# Sheet2.net
KiCad netlist of a schematic drawn in Altium Designer
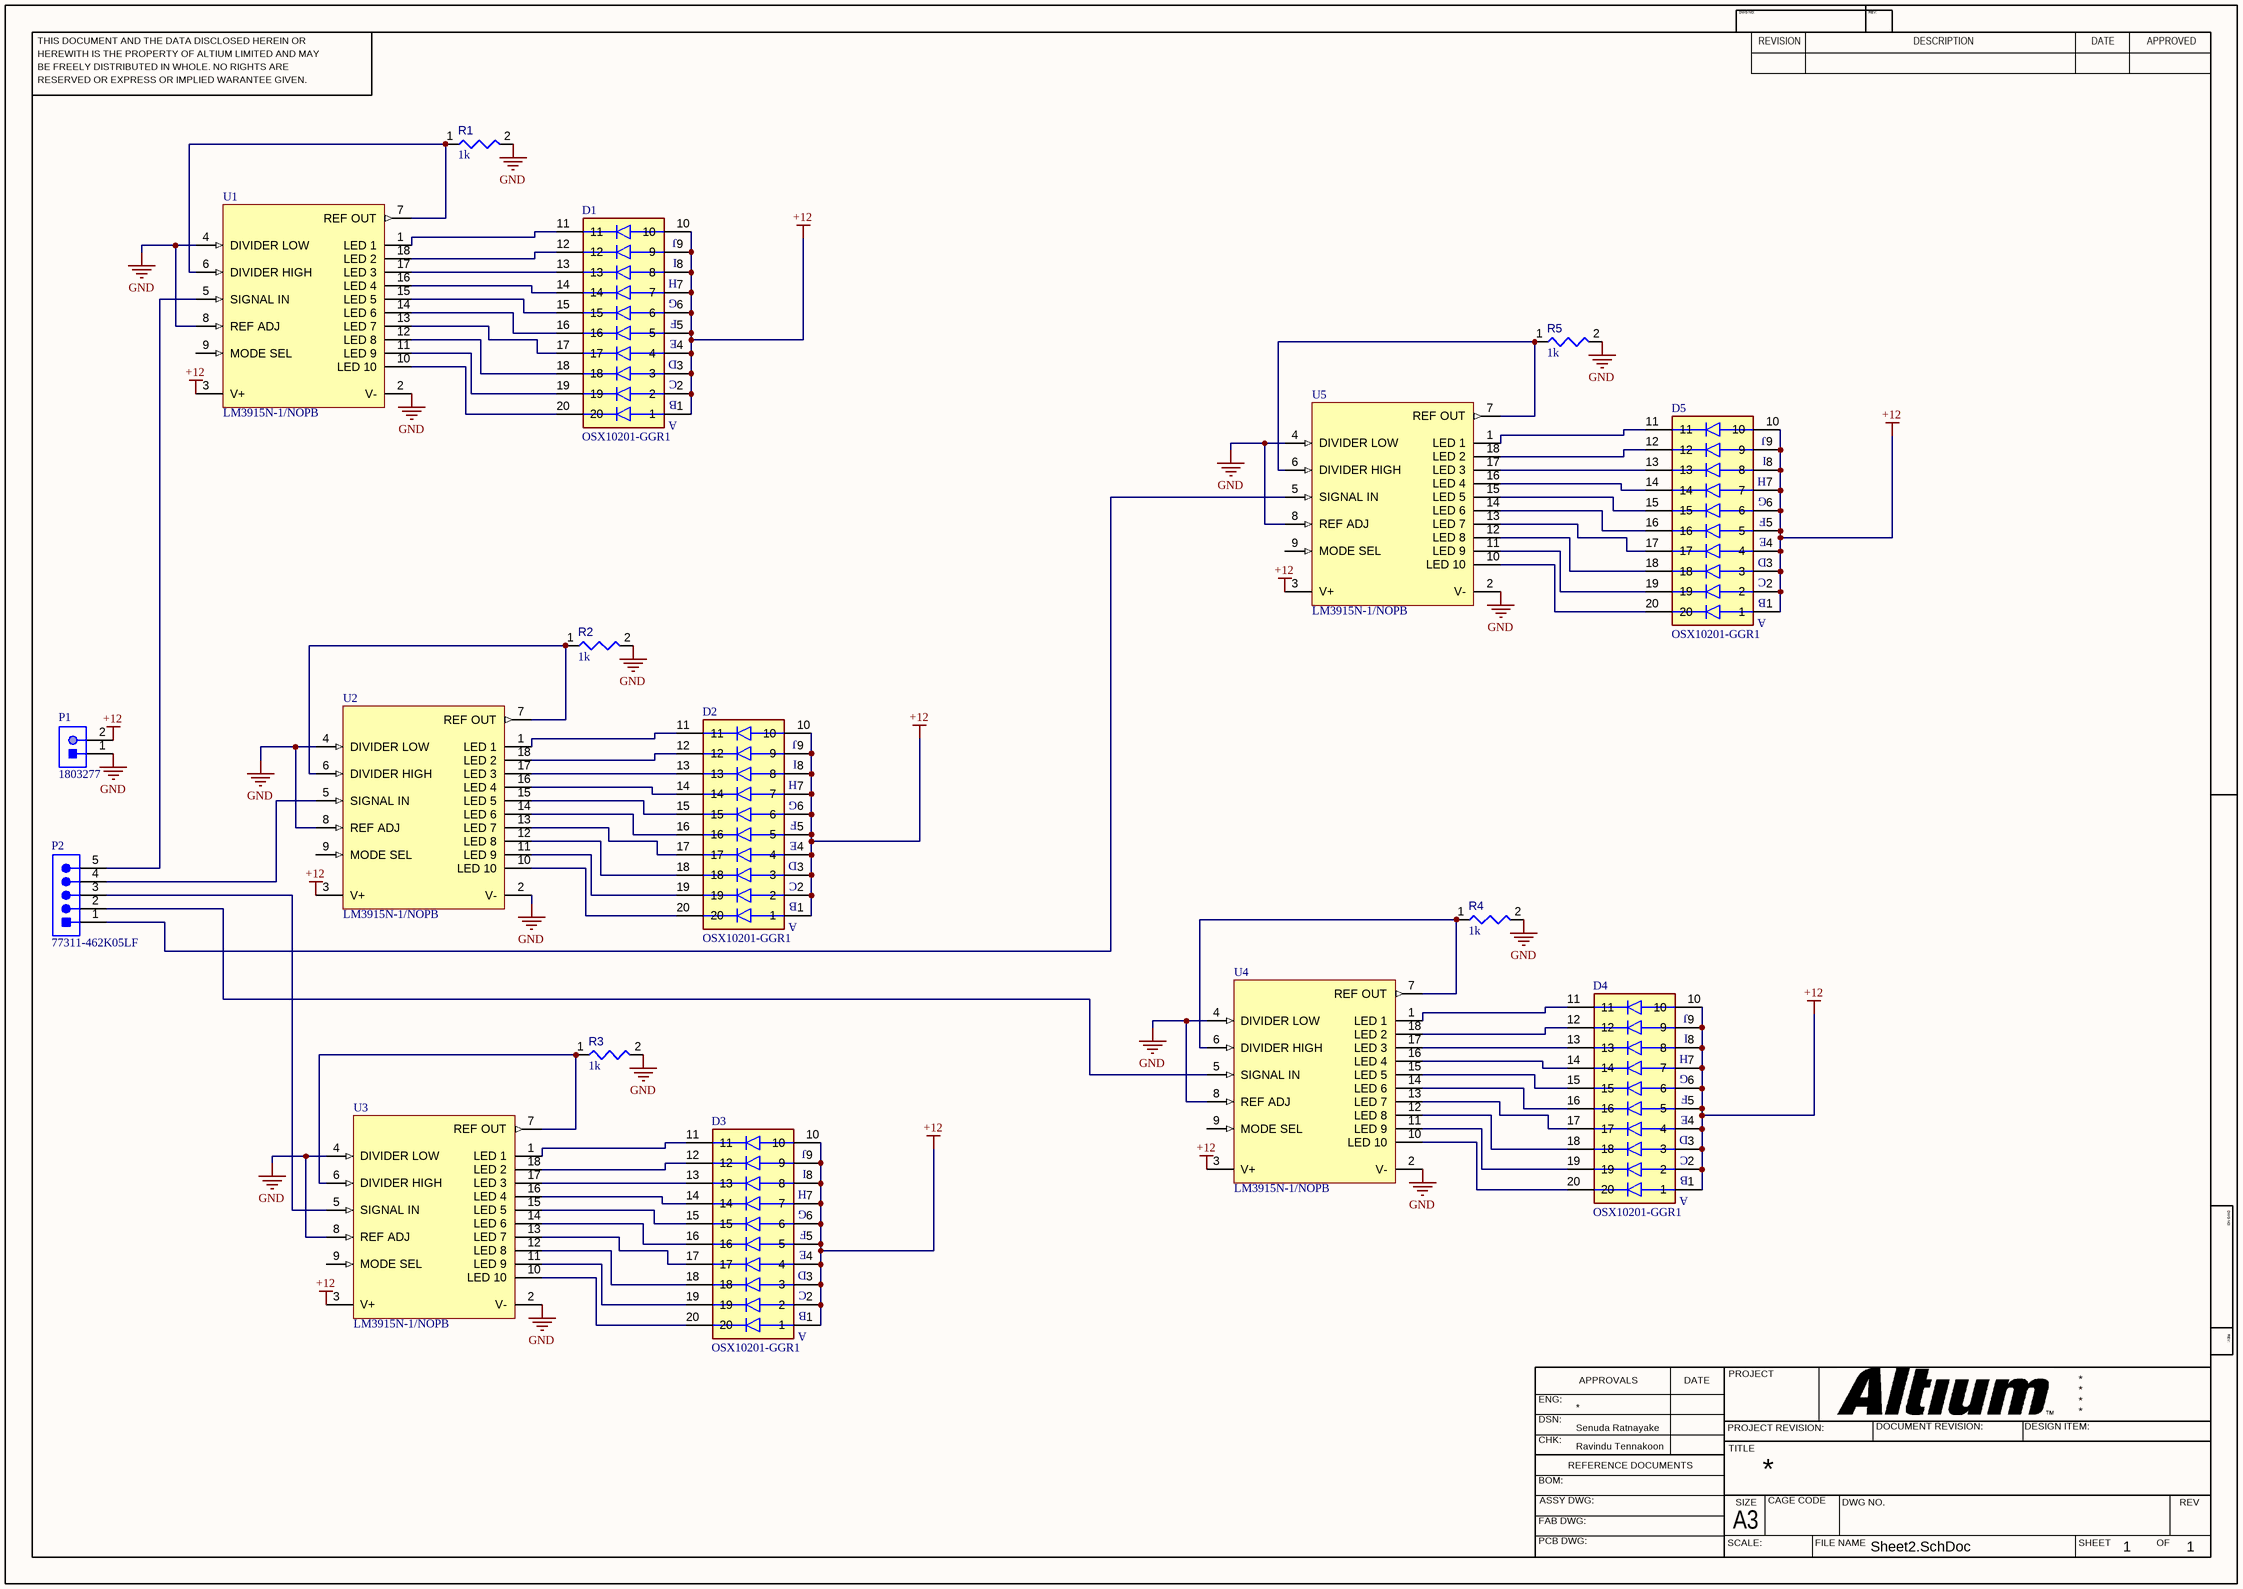
[diagram p0: Sheet2.SchDoc]

(export (version "E")
  (design (tool "Eeschema 10.0.6"))
  (components
    (comp (ref "D1")
      (value "OSX10201-GGR1")
      (footprint "DIP760W45P254L2550H790Q20")
      (description "Display: LED; bargraph; green (7x) / red (3x); 25.5x10.2x7.9mm")
      (fields (field (name "MF") "OptoSupply"))
      (libsource (lib "OSX10201-GGR1") (part "OSX10201-GGR1"))
    )
    (comp (ref "D2")
      (value "OSX10201-GGR1")
      (footprint "DIP760W45P254L2550H790Q20")
      (description "Display: LED; bargraph; green (7x) / red (3x); 25.5x10.2x7.9mm")
      (fields (field (name "MF") "OptoSupply"))
      (libsource (lib "OSX10201-GGR1") (part "OSX10201-GGR1"))
    )
    (comp (ref "D3")
      (value "OSX10201-GGR1")
      (footprint "DIP760W45P254L2550H790Q20")
      (description "Display: LED; bargraph; green (7x) / red (3x); 25.5x10.2x7.9mm")
      (fields (field (name "MF") "OptoSupply"))
      (libsource (lib "OSX10201-GGR1") (part "OSX10201-GGR1"))
    )
    (comp (ref "D4")
      (value "OSX10201-GGR1")
      (footprint "DIP760W45P254L2550H790Q20")
      (description "Display: LED; bargraph; green (7x) / red (3x); 25.5x10.2x7.9mm")
      (fields (field (name "MF") "OptoSupply"))
      (libsource (lib "OSX10201-GGR1") (part "OSX10201-GGR1"))
    )
    (comp (ref "D5")
      (value "OSX10201-GGR1")
      (footprint "DIP760W45P254L2550H790Q20")
      (description "Display: LED; bargraph; green (7x) / red (3x); 25.5x10.2x7.9mm")
      (fields (field (name "MF") "OptoSupply"))
      (libsource (lib "OSX10201-GGR1") (part "OSX10201-GGR1"))
    )
    (comp (ref "P1")
      (value "1803277")
      (footprint "PHOE-1803277_V")
      (description "Male Header, Pitch 3.81 mm, 1 x 2 Position, Height 7.25 mm, Tail Length 3.4 mm, RoHS, Bulk")
      (fields (field (name "MANUFACTURER") "Phoenix Contact"))
      (libsource (lib "Senuda Ratnayake") (part "CN-1P-M-R2"))
    )
    (comp (ref "P2")
      (value "77311-462K05LF")
      (footprint "FCI-77311-5_V")
      (fields (field (name "MANUFACTURER") "FCI Electronics"))
      (libsource (lib "Senuda Ratnayake") (part "CN-1P-M-R5"))
    )
    (comp (ref "R1")
      (value "1k")
      (footprint "RESA60-630X240")
      (description "Axial Resistor, 1 KOhm, +/- 1%, 250 mW, -55 to 155 degC, 2-Pin THD, RoHS, Bulk")
      (fields (field (name "TOLERANCE") "1%") (field (name "POWER") "250mW"))
      (libsource (lib "Senuda Ratnayake") (part "RES-2"))
    )
    (comp (ref "R2")
      (value "1k")
      (footprint "RESA60-630X240")
      (description "Axial Resistor, 1 KOhm, +/- 1%, 250 mW, -55 to 155 degC, 2-Pin THD, RoHS, Bulk")
      (fields (field (name "TOLERANCE") "1%") (field (name "POWER") "250mW"))
      (libsource (lib "Senuda Ratnayake") (part "RES-2"))
    )
    (comp (ref "R3")
      (value "1k")
      (footprint "RESA60-630X240")
      (description "Axial Resistor, 1 KOhm, +/- 1%, 250 mW, -55 to 155 degC, 2-Pin THD, RoHS, Bulk")
      (fields (field (name "TOLERANCE") "1%") (field (name "POWER") "250mW"))
      (libsource (lib "Senuda Ratnayake") (part "RES-2"))
    )
    (comp (ref "R4")
      (value "1k")
      (footprint "RESA60-630X240")
      (description "Axial Resistor, 1 KOhm, +/- 1%, 250 mW, -55 to 155 degC, 2-Pin THD, RoHS, Bulk")
      (fields (field (name "TOLERANCE") "1%") (field (name "POWER") "250mW"))
      (libsource (lib "Senuda Ratnayake") (part "RES-2"))
    )
    (comp (ref "R5")
      (value "1k")
      (footprint "RESA60-630X240")
      (description "Axial Resistor, 1 KOhm, +/- 1%, 250 mW, -55 to 155 degC, 2-Pin THD, RoHS, Bulk")
      (fields (field (name "TOLERANCE") "1%") (field (name "POWER") "250mW"))
      (libsource (lib "Senuda Ratnayake") (part "RES-2"))
    )
    (comp (ref "U1")
      (value "LM3915N-1/NOPB")
      (footprint "NFK0018A")
      (description "Dot/Bar Display Driver, 18-pin MDIP, Pb-Free")
      (fields (field (name "MANUFACTURER") "Texas Instruments"))
      (libsource (lib "Altium Content Vault") (part "IN-DD-LM3914-18"))
    )
    (comp (ref "U2")
      (value "LM3915N-1/NOPB")
      (footprint "NFK0018A")
      (description "Dot/Bar Display Driver, 18-pin MDIP, Pb-Free")
      (fields (field (name "MANUFACTURER") "Texas Instruments"))
      (libsource (lib "Altium Content Vault") (part "IN-DD-LM3914-18"))
    )
    (comp (ref "U3")
      (value "LM3915N-1/NOPB")
      (footprint "NFK0018A")
      (description "Dot/Bar Display Driver, 18-pin MDIP, Pb-Free")
      (fields (field (name "MANUFACTURER") "Texas Instruments"))
      (libsource (lib "Altium Content Vault") (part "IN-DD-LM3914-18"))
    )
    (comp (ref "U4")
      (value "LM3915N-1/NOPB")
      (footprint "NFK0018A")
      (description "Dot/Bar Display Driver, 18-pin MDIP, Pb-Free")
      (fields (field (name "MANUFACTURER") "Texas Instruments"))
      (libsource (lib "Altium Content Vault") (part "IN-DD-LM3914-18"))
    )
    (comp (ref "U5")
      (value "LM3915N-1/NOPB")
      (footprint "NFK0018A")
      (description "Dot/Bar Display Driver, 18-pin MDIP, Pb-Free")
      (fields (field (name "MANUFACTURER") "Texas Instruments"))
      (libsource (lib "Altium Content Vault") (part "IN-DD-LM3914-18"))
    )
  )
  (nets
    (net (code "1") (name "+12") (class "Default")
      (node (ref "D1") (pin "1") (pinfunction "1_1") (pintype "passive"))
      (node (ref "D1") (pin "10") (pinfunction "10_10") (pintype "passive"))
      (node (ref "D1") (pin "2") (pinfunction "2_2") (pintype "passive"))
      (node (ref "D1") (pin "3") (pinfunction "3_3") (pintype "passive"))
      (node (ref "D1") (pin "4") (pinfunction "4_4") (pintype "passive"))
      (node (ref "D1") (pin "5") (pinfunction "5_5") (pintype "passive"))
      (node (ref "D1") (pin "6") (pinfunction "6_6") (pintype "passive"))
      (node (ref "D1") (pin "7") (pinfunction "7_7") (pintype "passive"))
      (node (ref "D1") (pin "8") (pinfunction "8_8") (pintype "passive"))
      (node (ref "D1") (pin "9") (pinfunction "9_9") (pintype "passive"))
      (node (ref "D2") (pin "1") (pinfunction "1_1") (pintype "passive"))
      (node (ref "D2") (pin "10") (pinfunction "10_10") (pintype "passive"))
      (node (ref "D2") (pin "2") (pinfunction "2_2") (pintype "passive"))
      (node (ref "D2") (pin "3") (pinfunction "3_3") (pintype "passive"))
      (node (ref "D2") (pin "4") (pinfunction "4_4") (pintype "passive"))
      (node (ref "D2") (pin "5") (pinfunction "5_5") (pintype "passive"))
      (node (ref "D2") (pin "6") (pinfunction "6_6") (pintype "passive"))
      (node (ref "D2") (pin "7") (pinfunction "7_7") (pintype "passive"))
      (node (ref "D2") (pin "8") (pinfunction "8_8") (pintype "passive"))
      (node (ref "D2") (pin "9") (pinfunction "9_9") (pintype "passive"))
      (node (ref "D3") (pin "1") (pinfunction "1_1") (pintype "passive"))
      (node (ref "D3") (pin "10") (pinfunction "10_10") (pintype "passive"))
      (node (ref "D3") (pin "2") (pinfunction "2_2") (pintype "passive"))
      (node (ref "D3") (pin "3") (pinfunction "3_3") (pintype "passive"))
      (node (ref "D3") (pin "4") (pinfunction "4_4") (pintype "passive"))
      (node (ref "D3") (pin "5") (pinfunction "5_5") (pintype "passive"))
      (node (ref "D3") (pin "6") (pinfunction "6_6") (pintype "passive"))
      (node (ref "D3") (pin "7") (pinfunction "7_7") (pintype "passive"))
      (node (ref "D3") (pin "8") (pinfunction "8_8") (pintype "passive"))
      (node (ref "D3") (pin "9") (pinfunction "9_9") (pintype "passive"))
      (node (ref "D4") (pin "1") (pinfunction "1_1") (pintype "passive"))
      (node (ref "D4") (pin "10") (pinfunction "10_10") (pintype "passive"))
      (node (ref "D4") (pin "2") (pinfunction "2_2") (pintype "passive"))
      (node (ref "D4") (pin "3") (pinfunction "3_3") (pintype "passive"))
      (node (ref "D4") (pin "4") (pinfunction "4_4") (pintype "passive"))
      (node (ref "D4") (pin "5") (pinfunction "5_5") (pintype "passive"))
      (node (ref "D4") (pin "6") (pinfunction "6_6") (pintype "passive"))
      (node (ref "D4") (pin "7") (pinfunction "7_7") (pintype "passive"))
      (node (ref "D4") (pin "8") (pinfunction "8_8") (pintype "passive"))
      (node (ref "D4") (pin "9") (pinfunction "9_9") (pintype "passive"))
      (node (ref "D5") (pin "1") (pinfunction "1_1") (pintype "passive"))
      (node (ref "D5") (pin "10") (pinfunction "10_10") (pintype "passive"))
      (node (ref "D5") (pin "2") (pinfunction "2_2") (pintype "passive"))
      (node (ref "D5") (pin "3") (pinfunction "3_3") (pintype "passive"))
      (node (ref "D5") (pin "4") (pinfunction "4_4") (pintype "passive"))
      (node (ref "D5") (pin "5") (pinfunction "5_5") (pintype "passive"))
      (node (ref "D5") (pin "6") (pinfunction "6_6") (pintype "passive"))
      (node (ref "D5") (pin "7") (pinfunction "7_7") (pintype "passive"))
      (node (ref "D5") (pin "8") (pinfunction "8_8") (pintype "passive"))
      (node (ref "D5") (pin "9") (pinfunction "9_9") (pintype "passive"))
      (node (ref "P1") (pin "2") (pinfunction "2_2") (pintype "passive"))
      (node (ref "U1") (pin "3") (pinfunction "V+_3") (pintype "power_in"))
      (node (ref "U2") (pin "3") (pinfunction "V+_3") (pintype "power_in"))
      (node (ref "U3") (pin "3") (pinfunction "V+_3") (pintype "power_in"))
      (node (ref "U4") (pin "3") (pinfunction "V+_3") (pintype "power_in"))
      (node (ref "U5") (pin "3") (pinfunction "V+_3") (pintype "power_in"))
    )
    (net (code "2") (name "GND") (class "Default")
      (node (ref "P1") (pin "1") (pinfunction "1_1") (pintype "passive"))
      (node (ref "R1") (pin "2") (pinfunction "2_2") (pintype "passive"))
      (node (ref "R2") (pin "2") (pinfunction "2_2") (pintype "passive"))
      (node (ref "R3") (pin "2") (pinfunction "2_2") (pintype "passive"))
      (node (ref "R4") (pin "2") (pinfunction "2_2") (pintype "passive"))
      (node (ref "R5") (pin "2") (pinfunction "2_2") (pintype "passive"))
      (node (ref "U1") (pin "2") (pinfunction "V-_2") (pintype "power_in"))
      (node (ref "U1") (pin "4") (pinfunction "DIVIDER_LOW_4") (pintype "input"))
      (node (ref "U1") (pin "8") (pinfunction "REF_ADJ_8") (pintype "input"))
      (node (ref "U2") (pin "2") (pinfunction "V-_2") (pintype "power_in"))
      (node (ref "U2") (pin "4") (pinfunction "DIVIDER_LOW_4") (pintype "input"))
      (node (ref "U2") (pin "8") (pinfunction "REF_ADJ_8") (pintype "input"))
      (node (ref "U3") (pin "2") (pinfunction "V-_2") (pintype "power_in"))
      (node (ref "U3") (pin "4") (pinfunction "DIVIDER_LOW_4") (pintype "input"))
      (node (ref "U3") (pin "8") (pinfunction "REF_ADJ_8") (pintype "input"))
      (node (ref "U4") (pin "2") (pinfunction "V-_2") (pintype "power_in"))
      (node (ref "U4") (pin "4") (pinfunction "DIVIDER_LOW_4") (pintype "input"))
      (node (ref "U4") (pin "8") (pinfunction "REF_ADJ_8") (pintype "input"))
      (node (ref "U5") (pin "2") (pinfunction "V-_2") (pintype "power_in"))
      (node (ref "U5") (pin "4") (pinfunction "DIVIDER_LOW_4") (pintype "input"))
      (node (ref "U5") (pin "8") (pinfunction "REF_ADJ_8") (pintype "input"))
    )
    (net (code "3") (name "Net-(P2-CTS)") (class "Default")
      (node (ref "P2") (pin "5") (pinfunction "CTS_5") (pintype "passive"))
      (node (ref "U1") (pin "5") (pinfunction "SIGNAL_IN_5") (pintype "input"))
    )
    (net (code "4") (name "Net-(P2-DTR)") (class "Default")
      (node (ref "P2") (pin "1") (pinfunction "DTR_1") (pintype "passive"))
      (node (ref "U5") (pin "5") (pinfunction "SIGNAL_IN_5") (pintype "input"))
    )
    (net (code "5") (name "Net-(P2-RXI)") (class "Default")
      (node (ref "P2") (pin "2") (pinfunction "RXI_2") (pintype "passive"))
      (node (ref "U4") (pin "5") (pinfunction "SIGNAL_IN_5") (pintype "input"))
    )
    (net (code "6") (name "Net-(P2-TXO)") (class "Default")
      (node (ref "P2") (pin "3") (pinfunction "TXO_3") (pintype "passive"))
      (node (ref "U3") (pin "5") (pinfunction "SIGNAL_IN_5") (pintype "input"))
    )
    (net (code "7") (name "Net-(P2-VCC)") (class "Default")
      (node (ref "P2") (pin "4") (pinfunction "VCC_4") (pintype "passive"))
      (node (ref "U2") (pin "5") (pinfunction "SIGNAL_IN_5") (pintype "input"))
    )
    (net (code "8") (name "Net-(U1-DIVIDER_HIGH)") (class "Default")
      (node (ref "R1") (pin "1") (pinfunction "1_1") (pintype "passive"))
      (node (ref "U1") (pin "6") (pinfunction "DIVIDER_HIGH_6") (pintype "input"))
      (node (ref "U1") (pin "7") (pinfunction "REF_OUT_7") (pintype "output"))
    )
    (net (code "9") (name "Net-(U1-LED_1)") (class "Default")
      (node (ref "D1") (pin "11") (pinfunction "11_11") (pintype "passive"))
      (node (ref "U1") (pin "1") (pinfunction "LED_1_1") (pintype "open_collector"))
    )
    (net (code "10") (name "Net-(U1-LED_2)") (class "Default")
      (node (ref "D1") (pin "12") (pinfunction "12_12") (pintype "passive"))
      (node (ref "U1") (pin "18") (pinfunction "LED_2_18") (pintype "open_collector"))
    )
    (net (code "11") (name "Net-(U1-LED_3)") (class "Default")
      (node (ref "D1") (pin "13") (pinfunction "13_13") (pintype "passive"))
      (node (ref "U1") (pin "17") (pinfunction "LED_3_17") (pintype "open_collector"))
    )
    (net (code "12") (name "Net-(U1-LED_4)") (class "Default")
      (node (ref "D1") (pin "14") (pinfunction "14_14") (pintype "passive"))
      (node (ref "U1") (pin "16") (pinfunction "LED_4_16") (pintype "open_collector"))
    )
    (net (code "13") (name "Net-(U1-LED_5)") (class "Default")
      (node (ref "D1") (pin "15") (pinfunction "15_15") (pintype "passive"))
      (node (ref "U1") (pin "15") (pinfunction "LED_5_15") (pintype "open_collector"))
    )
    (net (code "14") (name "Net-(U1-LED_6)") (class "Default")
      (node (ref "D1") (pin "16") (pinfunction "16_16") (pintype "passive"))
      (node (ref "U1") (pin "14") (pinfunction "LED_6_14") (pintype "open_collector"))
    )
    (net (code "15") (name "Net-(U1-LED_7)") (class "Default")
      (node (ref "D1") (pin "17") (pinfunction "17_17") (pintype "passive"))
      (node (ref "U1") (pin "13") (pinfunction "LED_7_13") (pintype "open_collector"))
    )
    (net (code "16") (name "Net-(U1-LED_8)") (class "Default")
      (node (ref "D1") (pin "18") (pinfunction "18_18") (pintype "passive"))
      (node (ref "U1") (pin "12") (pinfunction "LED_8_12") (pintype "open_collector"))
    )
    (net (code "17") (name "Net-(U1-LED_9)") (class "Default")
      (node (ref "D1") (pin "19") (pinfunction "19_19") (pintype "passive"))
      (node (ref "U1") (pin "11") (pinfunction "LED_9_11") (pintype "open_collector"))
    )
    (net (code "18") (name "Net-(U1-LED_10)") (class "Default")
      (node (ref "D1") (pin "20") (pinfunction "20_20") (pintype "passive"))
      (node (ref "U1") (pin "10") (pinfunction "LED_10_10") (pintype "open_collector"))
    )
    (net (code "19") (name "Net-(U2-DIVIDER_HIGH)") (class "Default")
      (node (ref "R2") (pin "1") (pinfunction "1_1") (pintype "passive"))
      (node (ref "U2") (pin "6") (pinfunction "DIVIDER_HIGH_6") (pintype "input"))
      (node (ref "U2") (pin "7") (pinfunction "REF_OUT_7") (pintype "output"))
    )
    (net (code "20") (name "Net-(U2-LED_1)") (class "Default")
      (node (ref "D2") (pin "11") (pinfunction "11_11") (pintype "passive"))
      (node (ref "U2") (pin "1") (pinfunction "LED_1_1") (pintype "open_collector"))
    )
    (net (code "21") (name "Net-(U2-LED_2)") (class "Default")
      (node (ref "D2") (pin "12") (pinfunction "12_12") (pintype "passive"))
      (node (ref "U2") (pin "18") (pinfunction "LED_2_18") (pintype "open_collector"))
    )
    (net (code "22") (name "Net-(U2-LED_3)") (class "Default")
      (node (ref "D2") (pin "13") (pinfunction "13_13") (pintype "passive"))
      (node (ref "U2") (pin "17") (pinfunction "LED_3_17") (pintype "open_collector"))
    )
    (net (code "23") (name "Net-(U2-LED_4)") (class "Default")
      (node (ref "D2") (pin "14") (pinfunction "14_14") (pintype "passive"))
      (node (ref "U2") (pin "16") (pinfunction "LED_4_16") (pintype "open_collector"))
    )
    (net (code "24") (name "Net-(U2-LED_5)") (class "Default")
      (node (ref "D2") (pin "15") (pinfunction "15_15") (pintype "passive"))
      (node (ref "U2") (pin "15") (pinfunction "LED_5_15") (pintype "open_collector"))
    )
    (net (code "25") (name "Net-(U2-LED_6)") (class "Default")
      (node (ref "D2") (pin "16") (pinfunction "16_16") (pintype "passive"))
      (node (ref "U2") (pin "14") (pinfunction "LED_6_14") (pintype "open_collector"))
    )
    (net (code "26") (name "Net-(U2-LED_7)") (class "Default")
      (node (ref "D2") (pin "17") (pinfunction "17_17") (pintype "passive"))
      (node (ref "U2") (pin "13") (pinfunction "LED_7_13") (pintype "open_collector"))
    )
    (net (code "27") (name "Net-(U2-LED_8)") (class "Default")
      (node (ref "D2") (pin "18") (pinfunction "18_18") (pintype "passive"))
      (node (ref "U2") (pin "12") (pinfunction "LED_8_12") (pintype "open_collector"))
    )
    (net (code "28") (name "Net-(U2-LED_9)") (class "Default")
      (node (ref "D2") (pin "19") (pinfunction "19_19") (pintype "passive"))
      (node (ref "U2") (pin "11") (pinfunction "LED_9_11") (pintype "open_collector"))
    )
    (net (code "29") (name "Net-(U2-LED_10)") (class "Default")
      (node (ref "D2") (pin "20") (pinfunction "20_20") (pintype "passive"))
      (node (ref "U2") (pin "10") (pinfunction "LED_10_10") (pintype "open_collector"))
    )
    (net (code "30") (name "Net-(U3-DIVIDER_HIGH)") (class "Default")
      (node (ref "R3") (pin "1") (pinfunction "1_1") (pintype "passive"))
      (node (ref "U3") (pin "6") (pinfunction "DIVIDER_HIGH_6") (pintype "input"))
      (node (ref "U3") (pin "7") (pinfunction "REF_OUT_7") (pintype "output"))
    )
    (net (code "31") (name "Net-(U3-LED_1)") (class "Default")
      (node (ref "D3") (pin "11") (pinfunction "11_11") (pintype "passive"))
      (node (ref "U3") (pin "1") (pinfunction "LED_1_1") (pintype "open_collector"))
    )
    (net (code "32") (name "Net-(U3-LED_2)") (class "Default")
      (node (ref "D3") (pin "12") (pinfunction "12_12") (pintype "passive"))
      (node (ref "U3") (pin "18") (pinfunction "LED_2_18") (pintype "open_collector"))
    )
    (net (code "33") (name "Net-(U3-LED_3)") (class "Default")
      (node (ref "D3") (pin "13") (pinfunction "13_13") (pintype "passive"))
      (node (ref "U3") (pin "17") (pinfunction "LED_3_17") (pintype "open_collector"))
    )
    (net (code "34") (name "Net-(U3-LED_4)") (class "Default")
      (node (ref "D3") (pin "14") (pinfunction "14_14") (pintype "passive"))
      (node (ref "U3") (pin "16") (pinfunction "LED_4_16") (pintype "open_collector"))
    )
    (net (code "35") (name "Net-(U3-LED_5)") (class "Default")
      (node (ref "D3") (pin "15") (pinfunction "15_15") (pintype "passive"))
      (node (ref "U3") (pin "15") (pinfunction "LED_5_15") (pintype "open_collector"))
    )
    (net (code "36") (name "Net-(U3-LED_6)") (class "Default")
      (node (ref "D3") (pin "16") (pinfunction "16_16") (pintype "passive"))
      (node (ref "U3") (pin "14") (pinfunction "LED_6_14") (pintype "open_collector"))
    )
    (net (code "37") (name "Net-(U3-LED_7)") (class "Default")
      (node (ref "D3") (pin "17") (pinfunction "17_17") (pintype "passive"))
      (node (ref "U3") (pin "13") (pinfunction "LED_7_13") (pintype "open_collector"))
    )
    (net (code "38") (name "Net-(U3-LED_8)") (class "Default")
      (node (ref "D3") (pin "18") (pinfunction "18_18") (pintype "passive"))
      (node (ref "U3") (pin "12") (pinfunction "LED_8_12") (pintype "open_collector"))
    )
    (net (code "39") (name "Net-(U3-LED_9)") (class "Default")
      (node (ref "D3") (pin "19") (pinfunction "19_19") (pintype "passive"))
      (node (ref "U3") (pin "11") (pinfunction "LED_9_11") (pintype "open_collector"))
    )
    (net (code "40") (name "Net-(U3-LED_10)") (class "Default")
      (node (ref "D3") (pin "20") (pinfunction "20_20") (pintype "passive"))
      (node (ref "U3") (pin "10") (pinfunction "LED_10_10") (pintype "open_collector"))
    )
    (net (code "41") (name "Net-(U4-DIVIDER_HIGH)") (class "Default")
      (node (ref "R4") (pin "1") (pinfunction "1_1") (pintype "passive"))
      (node (ref "U4") (pin "6") (pinfunction "DIVIDER_HIGH_6") (pintype "input"))
      (node (ref "U4") (pin "7") (pinfunction "REF_OUT_7") (pintype "output"))
    )
    (net (code "42") (name "Net-(U4-LED_1)") (class "Default")
      (node (ref "D4") (pin "11") (pinfunction "11_11") (pintype "passive"))
      (node (ref "U4") (pin "1") (pinfunction "LED_1_1") (pintype "open_collector"))
    )
    (net (code "43") (name "Net-(U4-LED_2)") (class "Default")
      (node (ref "D4") (pin "12") (pinfunction "12_12") (pintype "passive"))
      (node (ref "U4") (pin "18") (pinfunction "LED_2_18") (pintype "open_collector"))
    )
    (net (code "44") (name "Net-(U4-LED_3)") (class "Default")
      (node (ref "D4") (pin "13") (pinfunction "13_13") (pintype "passive"))
      (node (ref "U4") (pin "17") (pinfunction "LED_3_17") (pintype "open_collector"))
    )
    (net (code "45") (name "Net-(U4-LED_4)") (class "Default")
      (node (ref "D4") (pin "14") (pinfunction "14_14") (pintype "passive"))
      (node (ref "U4") (pin "16") (pinfunction "LED_4_16") (pintype "open_collector"))
    )
    (net (code "46") (name "Net-(U4-LED_5)") (class "Default")
      (node (ref "D4") (pin "15") (pinfunction "15_15") (pintype "passive"))
      (node (ref "U4") (pin "15") (pinfunction "LED_5_15") (pintype "open_collector"))
    )
    (net (code "47") (name "Net-(U4-LED_6)") (class "Default")
      (node (ref "D4") (pin "16") (pinfunction "16_16") (pintype "passive"))
      (node (ref "U4") (pin "14") (pinfunction "LED_6_14") (pintype "open_collector"))
    )
    (net (code "48") (name "Net-(U4-LED_7)") (class "Default")
      (node (ref "D4") (pin "17") (pinfunction "17_17") (pintype "passive"))
      (node (ref "U4") (pin "13") (pinfunction "LED_7_13") (pintype "open_collector"))
    )
    (net (code "49") (name "Net-(U4-LED_8)") (class "Default")
      (node (ref "D4") (pin "18") (pinfunction "18_18") (pintype "passive"))
      (node (ref "U4") (pin "12") (pinfunction "LED_8_12") (pintype "open_collector"))
    )
    (net (code "50") (name "Net-(U4-LED_9)") (class "Default")
      (node (ref "D4") (pin "19") (pinfunction "19_19") (pintype "passive"))
      (node (ref "U4") (pin "11") (pinfunction "LED_9_11") (pintype "open_collector"))
    )
    (net (code "51") (name "Net-(U4-LED_10)") (class "Default")
      (node (ref "D4") (pin "20") (pinfunction "20_20") (pintype "passive"))
      (node (ref "U4") (pin "10") (pinfunction "LED_10_10") (pintype "open_collector"))
    )
    (net (code "52") (name "Net-(U5-DIVIDER_HIGH)") (class "Default")
      (node (ref "R5") (pin "1") (pinfunction "1_1") (pintype "passive"))
      (node (ref "U5") (pin "6") (pinfunction "DIVIDER_HIGH_6") (pintype "input"))
      (node (ref "U5") (pin "7") (pinfunction "REF_OUT_7") (pintype "output"))
    )
    (net (code "53") (name "Net-(U5-LED_1)") (class "Default")
      (node (ref "D5") (pin "11") (pinfunction "11_11") (pintype "passive"))
      (node (ref "U5") (pin "1") (pinfunction "LED_1_1") (pintype "open_collector"))
    )
    (net (code "54") (name "Net-(U5-LED_2)") (class "Default")
      (node (ref "D5") (pin "12") (pinfunction "12_12") (pintype "passive"))
      (node (ref "U5") (pin "18") (pinfunction "LED_2_18") (pintype "open_collector"))
    )
    (net (code "55") (name "Net-(U5-LED_3)") (class "Default")
      (node (ref "D5") (pin "13") (pinfunction "13_13") (pintype "passive"))
      (node (ref "U5") (pin "17") (pinfunction "LED_3_17") (pintype "open_collector"))
    )
    (net (code "56") (name "Net-(U5-LED_4)") (class "Default")
      (node (ref "D5") (pin "14") (pinfunction "14_14") (pintype "passive"))
      (node (ref "U5") (pin "16") (pinfunction "LED_4_16") (pintype "open_collector"))
    )
    (net (code "57") (name "Net-(U5-LED_5)") (class "Default")
      (node (ref "D5") (pin "15") (pinfunction "15_15") (pintype "passive"))
      (node (ref "U5") (pin "15") (pinfunction "LED_5_15") (pintype "open_collector"))
    )
    (net (code "58") (name "Net-(U5-LED_6)") (class "Default")
      (node (ref "D5") (pin "16") (pinfunction "16_16") (pintype "passive"))
      (node (ref "U5") (pin "14") (pinfunction "LED_6_14") (pintype "open_collector"))
    )
    (net (code "59") (name "Net-(U5-LED_7)") (class "Default")
      (node (ref "D5") (pin "17") (pinfunction "17_17") (pintype "passive"))
      (node (ref "U5") (pin "13") (pinfunction "LED_7_13") (pintype "open_collector"))
    )
    (net (code "60") (name "Net-(U5-LED_8)") (class "Default")
      (node (ref "D5") (pin "18") (pinfunction "18_18") (pintype "passive"))
      (node (ref "U5") (pin "12") (pinfunction "LED_8_12") (pintype "open_collector"))
    )
    (net (code "61") (name "Net-(U5-LED_9)") (class "Default")
      (node (ref "D5") (pin "19") (pinfunction "19_19") (pintype "passive"))
      (node (ref "U5") (pin "11") (pinfunction "LED_9_11") (pintype "open_collector"))
    )
    (net (code "62") (name "Net-(U5-LED_10)") (class "Default")
      (node (ref "D5") (pin "20") (pinfunction "20_20") (pintype "passive"))
      (node (ref "U5") (pin "10") (pinfunction "LED_10_10") (pintype "open_collector"))
    )
    (net (code "63") (name "unconnected-(U1-MODE_SEL-Pad9)") (class "Default")
      (node (ref "U1") (pin "9") (pinfunction "MODE_SEL_9") (pintype "input"))
    )
    (net (code "64") (name "unconnected-(U2-MODE_SEL-Pad9)") (class "Default")
      (node (ref "U2") (pin "9") (pinfunction "MODE_SEL_9") (pintype "input"))
    )
    (net (code "65") (name "unconnected-(U3-MODE_SEL-Pad9)") (class "Default")
      (node (ref "U3") (pin "9") (pinfunction "MODE_SEL_9") (pintype "input"))
    )
    (net (code "66") (name "unconnected-(U4-MODE_SEL-Pad9)") (class "Default")
      (node (ref "U4") (pin "9") (pinfunction "MODE_SEL_9") (pintype "input"))
    )
    (net (code "67") (name "unconnected-(U5-MODE_SEL-Pad9)") (class "Default")
      (node (ref "U5") (pin "9") (pinfunction "MODE_SEL_9") (pintype "input"))
    )
  )
)
